# Hecquyn_SCH_Proto1_210521.net
KiCad netlist of a schematic drawn in Altium Designer
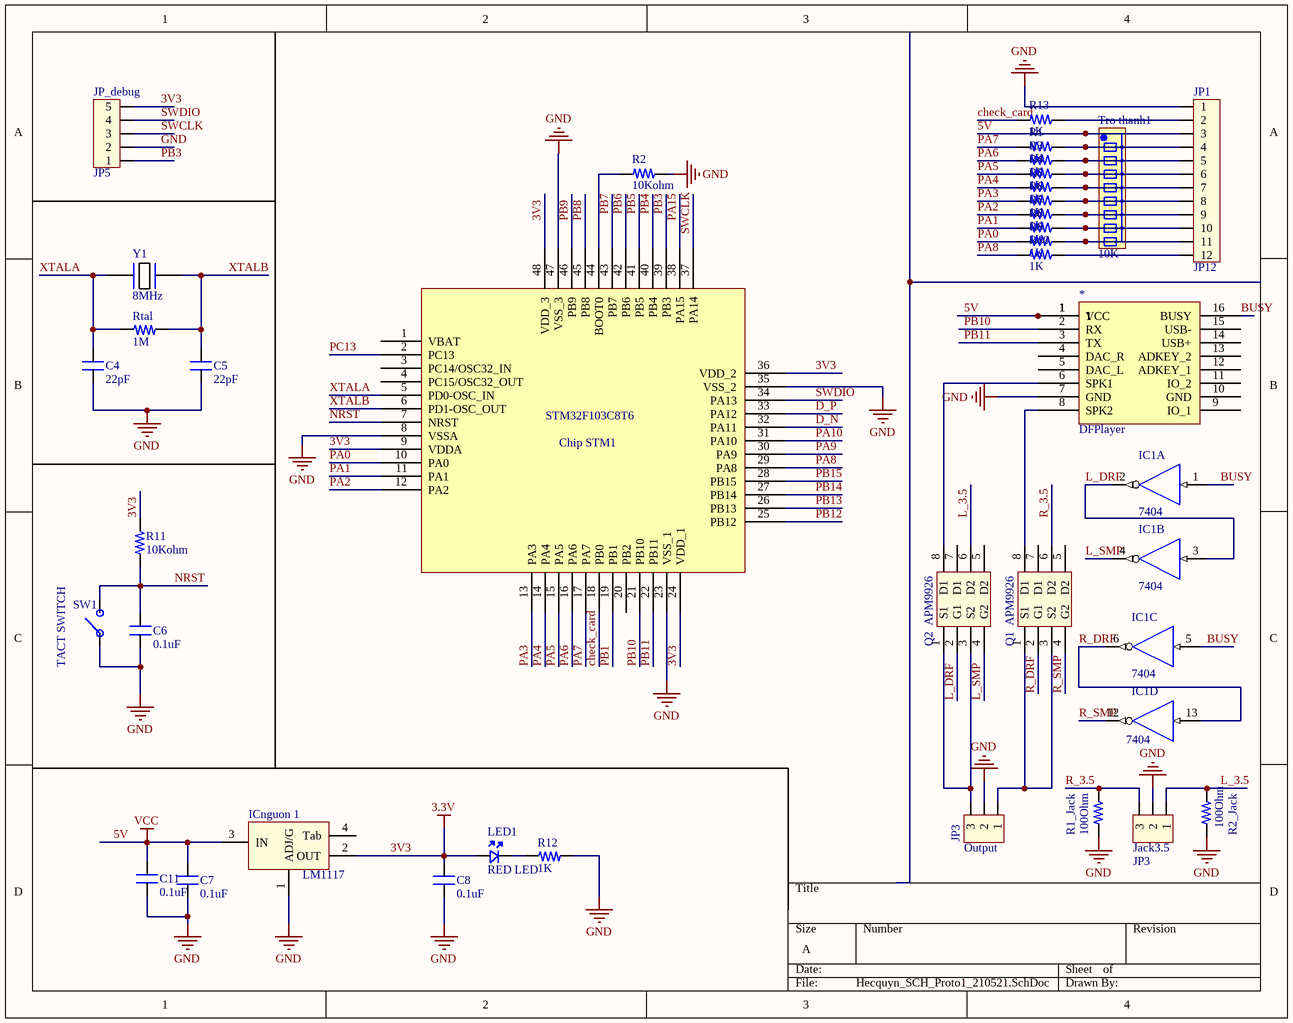
[diagram p0: Hecquyn_SCH_Proto1_210521.SchDoc]

(export (version "E")
  (design (tool "Eeschema 10.0.6"))
  (components
    (comp (ref "*")
      (value "DFPlayer")
      (footprint "DFplayer")
      (libsource (lib "Playersmd") (part "Component_1"))
    )
    (comp (ref "C4")
      (value "22pF")
      (footprint "CAP_0805")
      (description "22pF ±5% 50V Ceramic Capacitor C0G, NP0 0805 (2012 Metric)")
      (fields
        (field (name "MANUFACTURER") "KEMET")
        (field (name "MANUFACTURER PART NUMBER") "C0805C220J5GACTU")
      )
      (libsource (lib "STM_SCH_LIB") (part "CAP_22pF-50V-5%-0805"))
    )
    (comp (ref "C5")
      (value "22pF")
      (footprint "CAP_0805")
      (description "22pF ±5% 50V Ceramic Capacitor C0G, NP0 0805 (2012 Metric)")
      (fields
        (field (name "MANUFACTURER") "KEMET")
        (field (name "MANUFACTURER PART NUMBER") "C0805C220J5GACTU")
      )
      (libsource (lib "STM_SCH_LIB") (part "CAP_22pF-50V-5%-0805"))
    )
    (comp (ref "C6")
      (value "0.1uF")
      (footprint "CAP_0805")
      (description "0.1µF ±5% 50V Ceramic Capacitor X7R 0805 (2012 Metric)")
      (fields
        (field (name "MANUFACTURER") "KEMET")
        (field (name "MANUFACTURING PART NUMBER") "C0805C104J5RACTU")
      )
      (libsource (lib "STM_SCH_LIB") (part "CAP_0.1uF-50V-5%-0805"))
    )
    (comp (ref "C7")
      (value "0.1uF")
      (footprint "CAP_0805")
      (description "0.1µF ±5% 50V Ceramic Capacitor X7R 0805 (2012 Metric)")
      (fields
        (field (name "MANUFACTURER") "KEMET")
        (field (name "MANUFACTURING PART NUMBER") "C0805C104J5RACTU")
      )
      (libsource (lib "STM_SCH_LIB") (part "CAP_0.1uF-50V-5%-0805"))
    )
    (comp (ref "C8")
      (value "0.1uF")
      (footprint "CAP_0805")
      (description "0.1µF ±5% 50V Ceramic Capacitor X7R 0805 (2012 Metric)")
      (fields
        (field (name "MANUFACTURER") "KEMET")
        (field (name "MANUFACTURING PART NUMBER") "C0805C104J5RACTU")
      )
      (libsource (lib "STM_SCH_LIB") (part "CAP_0.1uF-50V-5%-0805"))
    )
    (comp (ref "C11")
      (value "0.1uF")
      (footprint "CAP_0805")
      (description "0.1µF ±5% 50V Ceramic Capacitor X7R 0805 (2012 Metric)")
      (fields
        (field (name "MANUFACTURER") "KEMET")
        (field (name "MANUFACTURING PART NUMBER") "C0805C104J5RACTU")
      )
      (libsource (lib "STM_SCH_LIB") (part "CAP_0.1uF-50V-5%-0805"))
    )
    (comp (ref "Chip STM1")
      (value "STM32F103C8T6")
      (footprint "LQFP-48_19.6_393_58X11_SMD")
      (description "ARM® Cortex®-M3 STM32F1 Microcontroller IC 32-Bit 72MHz 64KB (64K x 8) FLASH")
      (fields (field (name "MANUFACTURER") "STMicroelectronics"))
      (libsource (lib "STM_SCH_LIB") (part "IC-STM32F103C8T6 _1"))
    )
    (comp (ref "IC1")
      (value "7404")
      (footprint "DIP14/W0.3")
      (description "Hex Inverter")
      (libsource (lib "syhaunguyen") (part "7404"))
    )
    (comp (ref "ICnguon 1")
      (value "LM1117")
      (footprint "SOT223-4N")
      (description "3v3")
      (libsource (lib "syhaunguyen") (part "LM1117"))
    )
    (comp (ref "Jack3.5")
      (value "JP3")
      (footprint "CON3")
      (description "Connector 3")
      (libsource (lib "syhaunguyen") (part "Con3"))
    )
    (comp (ref "JP1")
      (value "JP12")
      (footprint "CON12")
      (description "Connector 12")
      (libsource (lib "syhaunguyen") (part "Con12"))
    )
    (comp (ref "JP_debug")
      (value "JP5")
      (footprint "CON5")
      (description "Connector 5")
      (libsource (lib "syhaunguyen") (part "Con5"))
    )
    (comp (ref "LED1")
      (value "RED LED")
      (footprint "LED_0805")
      (description "Red 621nm LED Indication - Discrete 2V 0805 (2012 Metric)")
      (fields
        (field (name "MANUFACTURER") "Lite-On Inc.")
        (field (name "MANUFACTURER PART NUMBER") "LTST-C170EKT")
      )
      (libsource (lib "STM_SCH_LIB") (part "LED-RED_10mA-0805"))
    )
    (comp (ref "Output")
      (value "JP3")
      (footprint "CON3")
      (description "Connector 3")
      (libsource (lib "syhaunguyen") (part "Con3"))
    )
    (comp (ref "Q1")
      (value "APM9926")
      (footprint "SO-8")
      (description "Dual P-Channel Enhancement Mode MOSFET")
      (libsource (lib "syhaunguyen") (part "APM4953"))
    )
    (comp (ref "Q2")
      (value "APM9926")
      (footprint "SO-8")
      (description "Dual P-Channel Enhancement Mode MOSFET")
      (libsource (lib "syhaunguyen") (part "APM4953"))
    )
    (comp (ref "R1")
      (value "1K")
      (footprint "RES_0805")
      (description "1 kOhms ±1% 0.125W, 1/8W Chip Resistor 0805 (2012 Metric) Moisture Resistant Thick Film")
      (fields (field (name "MANUFACTURER") "垈㎵á") (field (name "MANUFACTURER PART NUMBER") "RC0805FR-071KL"))
      (libsource (lib "STM_SCH_LIB") (part "RES_1K-0.125W-1%-0805"))
    )
    (comp (ref "R1_Jack")
      (value "100Ohm")
      (footprint "RES_0805")
      (description "1 kOhms ±1% 0.125W, 1/8W Chip Resistor 0805 (2012 Metric) Moisture Resistant Thick Film")
      (fields (field (name "MANUFACTURER") "垈㎵á") (field (name "MANUFACTURER PART NUMBER") "RC0805FR-071KL"))
      (libsource (lib "STM_SCH_LIB") (part "RES_1K-0.125W-1%-0805"))
    )
    (comp (ref "R2")
      (value "10Kohm")
      (footprint "RES_0805")
      (description "10 kOhms ±1% 0.125W, 1/8W Chip Resistor 0805 (2012 Metric) Moisture Resistant Thick Film")
      (fields
        (field (name "MANUFACTURER") "Yageo")
        (field (name "MANUFACTURING PART NUMBER") "RC0805FR-0710KL")
      )
      (libsource (lib "STM_SCH_LIB") (part "RES_10K-0.125W-1%-0805"))
    )
    (comp (ref "R2_Jack")
      (value "100Ohm")
      (footprint "RES_0805")
      (description "1 kOhms ±1% 0.125W, 1/8W Chip Resistor 0805 (2012 Metric) Moisture Resistant Thick Film")
      (fields (field (name "MANUFACTURER") "垈㎵á") (field (name "MANUFACTURER PART NUMBER") "RC0805FR-071KL"))
      (libsource (lib "STM_SCH_LIB") (part "RES_1K-0.125W-1%-0805"))
    )
    (comp (ref "R3")
      (value "1K")
      (footprint "RES_0805")
      (description "1 kOhms ±1% 0.125W, 1/8W Chip Resistor 0805 (2012 Metric) Moisture Resistant Thick Film")
      (fields (field (name "MANUFACTURER") "垈㎵á") (field (name "MANUFACTURER PART NUMBER") "RC0805FR-071KL"))
      (libsource (lib "STM_SCH_LIB") (part "RES_1K-0.125W-1%-0805"))
    )
    (comp (ref "R4")
      (value "1K")
      (footprint "RES_0805")
      (description "1 kOhms ±1% 0.125W, 1/8W Chip Resistor 0805 (2012 Metric) Moisture Resistant Thick Film")
      (fields (field (name "MANUFACTURER") "垈㎵á") (field (name "MANUFACTURER PART NUMBER") "RC0805FR-071KL"))
      (libsource (lib "STM_SCH_LIB") (part "RES_1K-0.125W-1%-0805"))
    )
    (comp (ref "R5")
      (value "1K")
      (footprint "RES_0805")
      (description "1 kOhms ±1% 0.125W, 1/8W Chip Resistor 0805 (2012 Metric) Moisture Resistant Thick Film")
      (fields (field (name "MANUFACTURER") "垈㎵á") (field (name "MANUFACTURER PART NUMBER") "RC0805FR-071KL"))
      (libsource (lib "STM_SCH_LIB") (part "RES_1K-0.125W-1%-0805"))
    )
    (comp (ref "R6")
      (value "1K")
      (footprint "RES_0805")
      (description "1 kOhms ±1% 0.125W, 1/8W Chip Resistor 0805 (2012 Metric) Moisture Resistant Thick Film")
      (fields (field (name "MANUFACTURER") "垈㎵á") (field (name "MANUFACTURER PART NUMBER") "RC0805FR-071KL"))
      (libsource (lib "STM_SCH_LIB") (part "RES_1K-0.125W-1%-0805"))
    )
    (comp (ref "R7")
      (value "1K")
      (footprint "RES_0805")
      (description "1 kOhms ±1% 0.125W, 1/8W Chip Resistor 0805 (2012 Metric) Moisture Resistant Thick Film")
      (fields (field (name "MANUFACTURER") "垈㎵á") (field (name "MANUFACTURER PART NUMBER") "RC0805FR-071KL"))
      (libsource (lib "STM_SCH_LIB") (part "RES_1K-0.125W-1%-0805"))
    )
    (comp (ref "R8")
      (value "1K")
      (footprint "RES_0805")
      (description "1 kOhms ±1% 0.125W, 1/8W Chip Resistor 0805 (2012 Metric) Moisture Resistant Thick Film")
      (fields (field (name "MANUFACTURER") "垈㎵á") (field (name "MANUFACTURER PART NUMBER") "RC0805FR-071KL"))
      (libsource (lib "STM_SCH_LIB") (part "RES_1K-0.125W-1%-0805"))
    )
    (comp (ref "R9")
      (value "1K")
      (footprint "RES_0805")
      (description "1 kOhms ±1% 0.125W, 1/8W Chip Resistor 0805 (2012 Metric) Moisture Resistant Thick Film")
      (fields (field (name "MANUFACTURER") "垈㎵á") (field (name "MANUFACTURER PART NUMBER") "RC0805FR-071KL"))
      (libsource (lib "STM_SCH_LIB") (part "RES_1K-0.125W-1%-0805"))
    )
    (comp (ref "R10")
      (value "1K")
      (footprint "RES_0805")
      (description "1 kOhms ±1% 0.125W, 1/8W Chip Resistor 0805 (2012 Metric) Moisture Resistant Thick Film")
      (fields (field (name "MANUFACTURER") "垈㎵á") (field (name "MANUFACTURER PART NUMBER") "RC0805FR-071KL"))
      (libsource (lib "STM_SCH_LIB") (part "RES_1K-0.125W-1%-0805"))
    )
    (comp (ref "R11")
      (value "10Kohm")
      (footprint "RES_0805")
      (fields
        (field (name "MANUFACTURER") "Rohm Semiconductor")
        (field (name "MANUFACTURING PART NUMBER") "KTR10EZPF1005")
      )
      (libsource (lib "STM_SCH_LIB") (part "RES_10MOHM-0.125W-1%-0805"))
    )
    (comp (ref "R12")
      (value "1K")
      (footprint "RES_0805")
      (description "1 kOhms ±1% 0.125W, 1/8W Chip Resistor 0805 (2012 Metric) Moisture Resistant Thick Film")
      (fields (field (name "MANUFACTURER") "垈㎵á") (field (name "MANUFACTURER PART NUMBER") "RC0805FR-071KL"))
      (libsource (lib "STM_SCH_LIB") (part "RES_1K-0.125W-1%-0805"))
    )
    (comp (ref "R13")
      (value "1K")
      (footprint "RES_0805")
      (description "1 kOhms ±1% 0.125W, 1/8W Chip Resistor 0805 (2012 Metric) Moisture Resistant Thick Film")
      (fields (field (name "MANUFACTURER") "垈㎵á") (field (name "MANUFACTURER PART NUMBER") "RC0805FR-071KL"))
      (libsource (lib "STM_SCH_LIB") (part "RES_1K-0.125W-1%-0805"))
    )
    (comp (ref "Rtal")
      (value "1M")
      (footprint "RES_0805")
      (fields
        (field (name "MANUFACTURER") "Rohm Semiconductor")
        (field (name "MANUFACTURING PART NUMBER") "KTR10EZPF1005")
      )
      (libsource (lib "STM_SCH_LIB") (part "RES_10MOHM-0.125W-1%-0805"))
    )
    (comp (ref "SW1")
      (value "TACT SWITCH")
      (footprint "SW_342_SMD")
      (description "Tactile Switch SPST-NO Top Actuated Surface Mount")
      (fields (field (name "MANUFACTURER") "C&K") (field (name "MANUFACTURING PART NUMBER") "KSR223GLFG"))
      (libsource (lib "STM_SCH_LIB") (part "SW_KSR223GLFG-SMD"))
    )
    (comp (ref "Tro thanh1")
      (value "10K")
      (footprint "RN8")
      (description "Resistor 8 (Thanh)")
      (libsource (lib "syhaunguyen") (part "RN8"))
    )
    (comp (ref "Y1")
      (value "8MHz")
      (footprint "XTAL_314_240X47_SMD")
      (description "Crystals 8MHz 22pF -20C 70C")
      (fields
        (field (name "MANUFACTURER") "IQD Frequency Products")
        (field (name "MANUFACTURING PART NUMBER") "LFXTAL030234Reel")
      )
      (libsource (lib "STM_SCH_LIB") (part "XTAL_8MHZ-LFXTAL030234"))
    )
  )
  (nets
    (net (code "1") (name "/BUSY") (class "Default")
      (node (ref "*") (pin "16") (pinfunction "BUSY_16") (pintype "passive"))
      (node (ref "IC1") (pin "1") (pinfunction "A_1") (pintype "input"))
      (node (ref "IC1") (pin "5") (pinfunction "A_5") (pintype "input"))
    )
    (net (code "2") (name "/D_N") (class "Default")
      (node (ref "Chip STM1") (pin "32") (pinfunction "PA11_32") (pintype "passive"))
    )
    (net (code "3") (name "/D_P") (class "Default")
      (node (ref "Chip STM1") (pin "33") (pinfunction "PA12_33") (pintype "passive"))
    )
    (net (code "4") (name "/L_3.5") (class "Default")
      (node (ref "Jack3.5") (pin "1") (pinfunction "1_1") (pintype "passive"))
      (node (ref "Q2") (pin "6") (pinfunction "D2_6") (pintype "passive"))
      (node (ref "R2_Jack") (pin "2") (pinfunction "2_2") (pintype "passive"))
    )
    (net (code "5") (name "/L_DRF") (class "Default")
      (node (ref "IC1") (pin "2") (pinfunction "~{O}_2") (pintype "output"))
      (node (ref "IC1") (pin "3") (pinfunction "A_3") (pintype "input"))
      (node (ref "Q2") (pin "2") (pinfunction "G1_2") (pintype "passive"))
    )
    (net (code "6") (name "/L_SMP") (class "Default")
      (node (ref "IC1") (pin "4") (pinfunction "~{O}_4") (pintype "output"))
      (node (ref "Q2") (pin "4") (pinfunction "G2_4") (pintype "passive"))
    )
    (net (code "7") (name "/NRST") (class "Default")
      (node (ref "C6") (pin "2") (pinfunction "2_2") (pintype "passive"))
      (node (ref "Chip STM1") (pin "7") (pinfunction "NRST_7") (pintype "passive"))
      (node (ref "R11") (pin "1") (pinfunction "1_1") (pintype "passive"))
      (node (ref "SW1") (pin "2") (pinfunction "2_2") (pintype "passive"))
    )
    (net (code "8") (name "/PA0") (class "Default")
      (node (ref "Chip STM1") (pin "10") (pinfunction "PA0_10") (pintype "passive"))
      (node (ref "R9") (pin "1") (pinfunction "1_1") (pintype "passive"))
    )
    (net (code "9") (name "/PA1") (class "Default")
      (node (ref "Chip STM1") (pin "11") (pinfunction "PA1_11") (pintype "passive"))
      (node (ref "R8") (pin "1") (pinfunction "1_1") (pintype "passive"))
    )
    (net (code "10") (name "/PA2") (class "Default")
      (node (ref "Chip STM1") (pin "12") (pinfunction "PA2_12") (pintype "passive"))
      (node (ref "R7") (pin "1") (pinfunction "1_1") (pintype "passive"))
    )
    (net (code "11") (name "/PA3") (class "Default")
      (node (ref "Chip STM1") (pin "13") (pinfunction "PA3_13") (pintype "passive"))
      (node (ref "R6") (pin "1") (pinfunction "1_1") (pintype "passive"))
    )
    (net (code "12") (name "/PA4") (class "Default")
      (node (ref "Chip STM1") (pin "14") (pinfunction "PA4_14") (pintype "passive"))
      (node (ref "R5") (pin "1") (pinfunction "1_1") (pintype "passive"))
    )
    (net (code "13") (name "/PA5") (class "Default")
      (node (ref "Chip STM1") (pin "15") (pinfunction "PA5_15") (pintype "passive"))
      (node (ref "R4") (pin "1") (pinfunction "1_1") (pintype "passive"))
    )
    (net (code "14") (name "/PA6") (class "Default")
      (node (ref "Chip STM1") (pin "16") (pinfunction "PA6_16") (pintype "passive"))
      (node (ref "R3") (pin "1") (pinfunction "1_1") (pintype "passive"))
    )
    (net (code "15") (name "/PA7") (class "Default")
      (node (ref "Chip STM1") (pin "17") (pinfunction "PA7_17") (pintype "passive"))
      (node (ref "R1") (pin "1") (pinfunction "1_1") (pintype "passive"))
    )
    (net (code "16") (name "/PA8") (class "Default")
      (node (ref "Chip STM1") (pin "29") (pinfunction "PA8_29") (pintype "passive"))
      (node (ref "R10") (pin "1") (pinfunction "1_1") (pintype "passive"))
    )
    (net (code "17") (name "/PA9") (class "Default")
      (node (ref "Chip STM1") (pin "30") (pinfunction "PA9_30") (pintype "passive"))
    )
    (net (code "18") (name "/PA10") (class "Default")
      (node (ref "Chip STM1") (pin "31") (pinfunction "PA10_31") (pintype "passive"))
    )
    (net (code "19") (name "/PA15") (class "Default")
      (node (ref "Chip STM1") (pin "38") (pinfunction "PA15_38") (pintype "passive"))
    )
    (net (code "20") (name "/PB1") (class "Default")
      (node (ref "Chip STM1") (pin "19") (pinfunction "PB1_19") (pintype "passive"))
    )
    (net (code "21") (name "/PB3") (class "Default")
      (node (ref "Chip STM1") (pin "39") (pinfunction "PB3_39") (pintype "passive"))
      (node (ref "JP_debug") (pin "1") (pinfunction "1_1") (pintype "passive"))
    )
    (net (code "22") (name "/PB4") (class "Default")
      (node (ref "Chip STM1") (pin "40") (pinfunction "PB4_40") (pintype "passive"))
    )
    (net (code "23") (name "/PB5") (class "Default")
      (node (ref "Chip STM1") (pin "41") (pinfunction "PB5_41") (pintype "passive"))
    )
    (net (code "24") (name "/PB6") (class "Default")
      (node (ref "Chip STM1") (pin "42") (pinfunction "PB6_42") (pintype "passive"))
    )
    (net (code "25") (name "/PB7") (class "Default")
      (node (ref "Chip STM1") (pin "43") (pinfunction "PB7_43") (pintype "passive"))
    )
    (net (code "26") (name "/PB8") (class "Default")
      (node (ref "Chip STM1") (pin "45") (pinfunction "PB8_45") (pintype "passive"))
    )
    (net (code "27") (name "/PB9") (class "Default")
      (node (ref "Chip STM1") (pin "46") (pinfunction "PB9_46") (pintype "passive"))
    )
    (net (code "28") (name "/PB10") (class "Default")
      (node (ref "*") (pin "2") (pinfunction "RX_2") (pintype "passive"))
      (node (ref "Chip STM1") (pin "21") (pinfunction "PB10_21") (pintype "passive"))
    )
    (net (code "29") (name "/PB11") (class "Default")
      (node (ref "*") (pin "3") (pinfunction "TX_3") (pintype "passive"))
      (node (ref "Chip STM1") (pin "22") (pinfunction "PB11_22") (pintype "passive"))
    )
    (net (code "30") (name "/PB12") (class "Default")
      (node (ref "Chip STM1") (pin "25") (pinfunction "PB12_25") (pintype "passive"))
    )
    (net (code "31") (name "/PB13") (class "Default")
      (node (ref "Chip STM1") (pin "26") (pinfunction "PB13_26") (pintype "passive"))
    )
    (net (code "32") (name "/PB14") (class "Default")
      (node (ref "Chip STM1") (pin "27") (pinfunction "PB14_27") (pintype "passive"))
    )
    (net (code "33") (name "/PB15") (class "Default")
      (node (ref "Chip STM1") (pin "28") (pinfunction "PB15_28") (pintype "passive"))
    )
    (net (code "34") (name "/PC13") (class "Default")
      (node (ref "Chip STM1") (pin "2") (pinfunction "PC13_2") (pintype "passive"))
    )
    (net (code "35") (name "/R_3.5") (class "Default")
      (node (ref "Jack3.5") (pin "3") (pinfunction "3_3") (pintype "passive"))
      (node (ref "Q1") (pin "6") (pinfunction "D2_6") (pintype "passive"))
      (node (ref "R1_Jack") (pin "2") (pinfunction "2_2") (pintype "passive"))
    )
    (net (code "36") (name "/R_DRF") (class "Default")
      (node (ref "IC1") (pin "13") (pinfunction "A_13") (pintype "input"))
      (node (ref "IC1") (pin "6") (pinfunction "~{O}_6") (pintype "output"))
      (node (ref "Q1") (pin "2") (pinfunction "G1_2") (pintype "passive"))
    )
    (net (code "37") (name "/R_SMP") (class "Default")
      (node (ref "IC1") (pin "12") (pinfunction "~{O}_12") (pintype "output"))
      (node (ref "Q1") (pin "4") (pinfunction "G2_4") (pintype "passive"))
    )
    (net (code "38") (name "/SWCLK") (class "Default")
      (node (ref "Chip STM1") (pin "37") (pinfunction "PA14_37") (pintype "passive"))
      (node (ref "JP_debug") (pin "3") (pinfunction "3_3") (pintype "passive"))
    )
    (net (code "39") (name "/SWDIO") (class "Default")
      (node (ref "Chip STM1") (pin "34") (pinfunction "PA13_34") (pintype "passive"))
      (node (ref "JP_debug") (pin "4") (pinfunction "4_4") (pintype "passive"))
    )
    (net (code "40") (name "/XTALA") (class "Default")
      (node (ref "C4") (pin "2") (pinfunction "2_2") (pintype "passive"))
      (node (ref "Chip STM1") (pin "5") (pinfunction "PD0-OSC_IN_5") (pintype "passive"))
      (node (ref "Rtal") (pin "2") (pinfunction "2_2") (pintype "passive"))
      (node (ref "Y1") (pin "1") (pinfunction "1_1") (pintype "passive"))
    )
    (net (code "41") (name "/XTALB") (class "Default")
      (node (ref "C5") (pin "2") (pinfunction "2_2") (pintype "passive"))
      (node (ref "Chip STM1") (pin "6") (pinfunction "PD1-OSC_OUT_6") (pintype "passive"))
      (node (ref "Rtal") (pin "1") (pinfunction "1_1") (pintype "passive"))
      (node (ref "Y1") (pin "2") (pinfunction "2_2") (pintype "passive"))
    )
    (net (code "42") (name "/check_card") (class "Default")
      (node (ref "Chip STM1") (pin "18") (pinfunction "PB0_18") (pintype "passive"))
      (node (ref "R13") (pin "1") (pinfunction "1_1") (pintype "passive"))
    )
    (net (code "43") (name "3.3V") (class "Default")
      (node (ref "C8") (pin "2") (pinfunction "2_2") (pintype "passive"))
      (node (ref "Chip STM1") (pin "24") (pinfunction "VDD_1_24") (pintype "passive"))
      (node (ref "Chip STM1") (pin "36") (pinfunction "VDD_2_36") (pintype "passive"))
      (node (ref "Chip STM1") (pin "48") (pinfunction "VDD_3_48") (pintype "passive"))
      (node (ref "Chip STM1") (pin "9") (pinfunction "VDDA_9") (pintype "passive"))
      (node (ref "ICnguon 1") (pin "2") (pinfunction "OUT_2") (pintype "passive"))
      (node (ref "JP_debug") (pin "5") (pinfunction "5_5") (pintype "passive"))
      (node (ref "LED1") (pin "A") (pinfunction "A_A") (pintype "passive"))
      (node (ref "R11") (pin "2") (pinfunction "2_2") (pintype "passive"))
    )
    (net (code "44") (name "GND") (class "Default")
      (node (ref "*") (pin "7") (pinfunction "GND_7") (pintype "passive"))
      (node (ref "C11") (pin "1") (pinfunction "1_1") (pintype "passive"))
      (node (ref "C4") (pin "1") (pinfunction "1_1") (pintype "passive"))
      (node (ref "C5") (pin "1") (pinfunction "1_1") (pintype "passive"))
      (node (ref "C6") (pin "1") (pinfunction "1_1") (pintype "passive"))
      (node (ref "C7") (pin "1") (pinfunction "1_1") (pintype "passive"))
      (node (ref "C8") (pin "1") (pinfunction "1_1") (pintype "passive"))
      (node (ref "Chip STM1") (pin "23") (pinfunction "VSS_1_23") (pintype "passive"))
      (node (ref "Chip STM1") (pin "35") (pinfunction "VSS_2_35") (pintype "passive"))
      (node (ref "Chip STM1") (pin "47") (pinfunction "VSS_3_47") (pintype "passive"))
      (node (ref "Chip STM1") (pin "8") (pinfunction "VSSA_8") (pintype "passive"))
      (node (ref "IC1") (pin "7") (pinfunction "GND_7") (pintype "power_in"))
      (node (ref "ICnguon 1") (pin "1") (pinfunction "ADJ/G_1") (pintype "passive"))
      (node (ref "JP1") (pin "1") (pinfunction "1_1") (pintype "passive"))
      (node (ref "JP_debug") (pin "2") (pinfunction "2_2") (pintype "passive"))
      (node (ref "Jack3.5") (pin "2") (pinfunction "2_2") (pintype "passive"))
      (node (ref "Output") (pin "2") (pinfunction "2_2") (pintype "passive"))
      (node (ref "R12") (pin "1") (pinfunction "1_1") (pintype "passive"))
      (node (ref "R1_Jack") (pin "1") (pinfunction "1_1") (pintype "passive"))
      (node (ref "R2") (pin "2") (pinfunction "2_2") (pintype "passive"))
      (node (ref "R2_Jack") (pin "1") (pinfunction "1_1") (pintype "passive"))
      (node (ref "SW1") (pin "1") (pinfunction "1_1") (pintype "passive"))
    )
    (net (code "45") (name "Net-(*-SPK1)") (class "Default")
      (node (ref "*") (pin "6") (pinfunction "SPK1_6") (pintype "passive"))
      (node (ref "Q2") (pin "8") (pinfunction "D1_8") (pintype "passive"))
    )
    (net (code "46") (name "Net-(*-SPK2)") (class "Default")
      (node (ref "*") (pin "8") (pinfunction "SPK2_8") (pintype "passive"))
      (node (ref "Q1") (pin "8") (pinfunction "D1_8") (pintype "passive"))
    )
    (net (code "47") (name "Net-(Chip STM1-BOOT0)") (class "Default")
      (node (ref "Chip STM1") (pin "44") (pinfunction "BOOT0_44") (pintype "passive"))
      (node (ref "R2") (pin "1") (pinfunction "1_1") (pintype "passive"))
    )
    (net (code "48") (name "Net-(JP1-Pad2)") (class "Default")
      (node (ref "JP1") (pin "2") (pinfunction "2_2") (pintype "passive"))
      (node (ref "R13") (pin "2") (pinfunction "2_2") (pintype "passive"))
    )
    (net (code "49") (name "Net-(JP1-Pad4)") (class "Default")
      (node (ref "JP1") (pin "4") (pinfunction "4_4") (pintype "passive"))
      (node (ref "R1") (pin "2") (pinfunction "2_2") (pintype "passive"))
      (node (ref "Tro thanh1") (pin "2") (pinfunction "2_2") (pintype "passive"))
    )
    (net (code "50") (name "Net-(JP1-Pad5)") (class "Default")
      (node (ref "JP1") (pin "5") (pinfunction "5_5") (pintype "passive"))
      (node (ref "R3") (pin "2") (pinfunction "2_2") (pintype "passive"))
      (node (ref "Tro thanh1") (pin "3") (pinfunction "3_3") (pintype "passive"))
    )
    (net (code "51") (name "Net-(JP1-Pad6)") (class "Default")
      (node (ref "JP1") (pin "6") (pinfunction "6_6") (pintype "passive"))
      (node (ref "R4") (pin "2") (pinfunction "2_2") (pintype "passive"))
      (node (ref "Tro thanh1") (pin "4") (pinfunction "4_4") (pintype "passive"))
    )
    (net (code "52") (name "Net-(JP1-Pad7)") (class "Default")
      (node (ref "JP1") (pin "7") (pinfunction "7_7") (pintype "passive"))
      (node (ref "R5") (pin "2") (pinfunction "2_2") (pintype "passive"))
      (node (ref "Tro thanh1") (pin "5") (pinfunction "5_5") (pintype "passive"))
    )
    (net (code "53") (name "Net-(JP1-Pad8)") (class "Default")
      (node (ref "JP1") (pin "8") (pinfunction "8_8") (pintype "passive"))
      (node (ref "R6") (pin "2") (pinfunction "2_2") (pintype "passive"))
      (node (ref "Tro thanh1") (pin "6") (pinfunction "6_6") (pintype "passive"))
    )
    (net (code "54") (name "Net-(JP1-Pad9)") (class "Default")
      (node (ref "JP1") (pin "9") (pinfunction "9_9") (pintype "passive"))
      (node (ref "R7") (pin "2") (pinfunction "2_2") (pintype "passive"))
      (node (ref "Tro thanh1") (pin "7") (pinfunction "7_7") (pintype "passive"))
    )
    (net (code "55") (name "Net-(JP1-Pad10)") (class "Default")
      (node (ref "JP1") (pin "10") (pinfunction "10_10") (pintype "passive"))
      (node (ref "R8") (pin "2") (pinfunction "2_2") (pintype "passive"))
      (node (ref "Tro thanh1") (pin "8") (pinfunction "8_8") (pintype "passive"))
    )
    (net (code "56") (name "Net-(JP1-Pad11)") (class "Default")
      (node (ref "JP1") (pin "11") (pinfunction "11_11") (pintype "passive"))
      (node (ref "R9") (pin "2") (pinfunction "2_2") (pintype "passive"))
      (node (ref "Tro thanh1") (pin "9") (pinfunction "9_9") (pintype "passive"))
    )
    (net (code "57") (name "Net-(JP1-Pad12)") (class "Default")
      (node (ref "JP1") (pin "12") (pinfunction "12_12") (pintype "passive"))
      (node (ref "R10") (pin "2") (pinfunction "2_2") (pintype "passive"))
    )
    (net (code "58") (name "Net-(LED1-PadK)") (class "Default")
      (node (ref "LED1") (pin "K") (pinfunction "K_K") (pintype "passive"))
      (node (ref "R12") (pin "2") (pinfunction "2_2") (pintype "passive"))
    )
    (net (code "59") (name "Net-(Q1-S1)") (class "Default")
      (node (ref "Output") (pin "1") (pinfunction "1_1") (pintype "passive"))
      (node (ref "Q1") (pin "1") (pinfunction "S1_1") (pintype "passive"))
      (node (ref "Q1") (pin "3") (pinfunction "S2_3") (pintype "passive"))
    )
    (net (code "60") (name "Net-(Q2-S1)") (class "Default")
      (node (ref "Output") (pin "3") (pinfunction "3_3") (pintype "passive"))
      (node (ref "Q2") (pin "1") (pinfunction "S1_1") (pintype "passive"))
      (node (ref "Q2") (pin "3") (pinfunction "S2_3") (pintype "passive"))
    )
    (net (code "61") (name "VCC") (class "Default")
      (node (ref "*") (pin "1") (pinfunction "1_1") (pintype "passive"))
      (node (ref "C11") (pin "2") (pinfunction "2_2") (pintype "passive"))
      (node (ref "C7") (pin "2") (pinfunction "2_2") (pintype "passive"))
      (node (ref "IC1") (pin "14") (pinfunction "VCC_14") (pintype "power_in"))
      (node (ref "ICnguon 1") (pin "3") (pinfunction "IN_3") (pintype "passive"))
      (node (ref "JP1") (pin "3") (pinfunction "3_3") (pintype "passive"))
      (node (ref "Tro thanh1") (pin "1") (pinfunction "1_1") (pintype "passive"))
    )
    (net (code "62") (name "unconnected-(*-ADKEY_1-Pad12)") (class "Default")
      (node (ref "*") (pin "12") (pinfunction "ADKEY_1_12") (pintype "passive"))
    )
    (net (code "63") (name "unconnected-(*-ADKEY_2-Pad13)") (class "Default")
      (node (ref "*") (pin "13") (pinfunction "ADKEY_2_13") (pintype "passive"))
    )
    (net (code "64") (name "unconnected-(*-DAC_L-Pad5)") (class "Default")
      (node (ref "*") (pin "5") (pinfunction "DAC_L_5") (pintype "passive"))
    )
    (net (code "65") (name "unconnected-(*-DAC_R-Pad4)") (class "Default")
      (node (ref "*") (pin "4") (pinfunction "DAC_R_4") (pintype "passive"))
    )
    (net (code "66") (name "unconnected-(*-GND-Pad10)") (class "Default")
      (node (ref "*") (pin "10") (pinfunction "GND_10") (pintype "passive"))
    )
    (net (code "67") (name "unconnected-(*-IO_1-Pad9)") (class "Default")
      (node (ref "*") (pin "9") (pinfunction "IO_1_9") (pintype "passive"))
    )
    (net (code "68") (name "unconnected-(*-IO_2-Pad11)") (class "Default")
      (node (ref "*") (pin "11") (pinfunction "IO_2_11") (pintype "passive"))
    )
    (net (code "69") (name "unconnected-(*-USB+-Pad14)") (class "Default")
      (node (ref "*") (pin "14") (pinfunction "USB+_14") (pintype "passive"))
    )
    (net (code "70") (name "unconnected-(*-USB--Pad15)") (class "Default")
      (node (ref "*") (pin "15") (pinfunction "USB-_15") (pintype "passive"))
    )
    (net (code "71") (name "unconnected-(Chip STM1-PB2-Pad20)") (class "Default")
      (node (ref "Chip STM1") (pin "20") (pinfunction "PB2_20") (pintype "passive"))
    )
    (net (code "72") (name "unconnected-(Chip STM1-PC14{slash}OSC32_IN-Pad3)") (class "Default")
      (node (ref "Chip STM1") (pin "3") (pinfunction "PC14/OSC32_IN_3") (pintype "passive"))
    )
    (net (code "73") (name "unconnected-(Chip STM1-PC15{slash}OSC32_OUT-Pad4)") (class "Default")
      (node (ref "Chip STM1") (pin "4") (pinfunction "PC15/OSC32_OUT_4") (pintype "passive"))
    )
    (net (code "74") (name "unconnected-(Chip STM1-VBAT-Pad1)") (class "Default")
      (node (ref "Chip STM1") (pin "1") (pinfunction "VBAT_1") (pintype "passive"))
    )
    (net (code "75") (name "unconnected-(ICnguon 1-Tab-Pad4)") (class "Default")
      (node (ref "ICnguon 1") (pin "4") (pinfunction "Tab_4") (pintype "passive"))
    )
    (net (code "76") (name "unconnected-(Q1-D1-Pad7)") (class "Default")
      (node (ref "Q1") (pin "7") (pinfunction "D1_7") (pintype "passive"))
    )
    (net (code "77") (name "unconnected-(Q1-D2-Pad5)") (class "Default")
      (node (ref "Q1") (pin "5") (pinfunction "D2_5") (pintype "passive"))
    )
    (net (code "78") (name "unconnected-(Q2-D1-Pad7)") (class "Default")
      (node (ref "Q2") (pin "7") (pinfunction "D1_7") (pintype "passive"))
    )
    (net (code "79") (name "unconnected-(Q2-D2-Pad5)") (class "Default")
      (node (ref "Q2") (pin "5") (pinfunction "D2_5") (pintype "passive"))
    )
  )
)
